# 04_-Power.net
KiCad netlist of a schematic drawn in Altium Designer
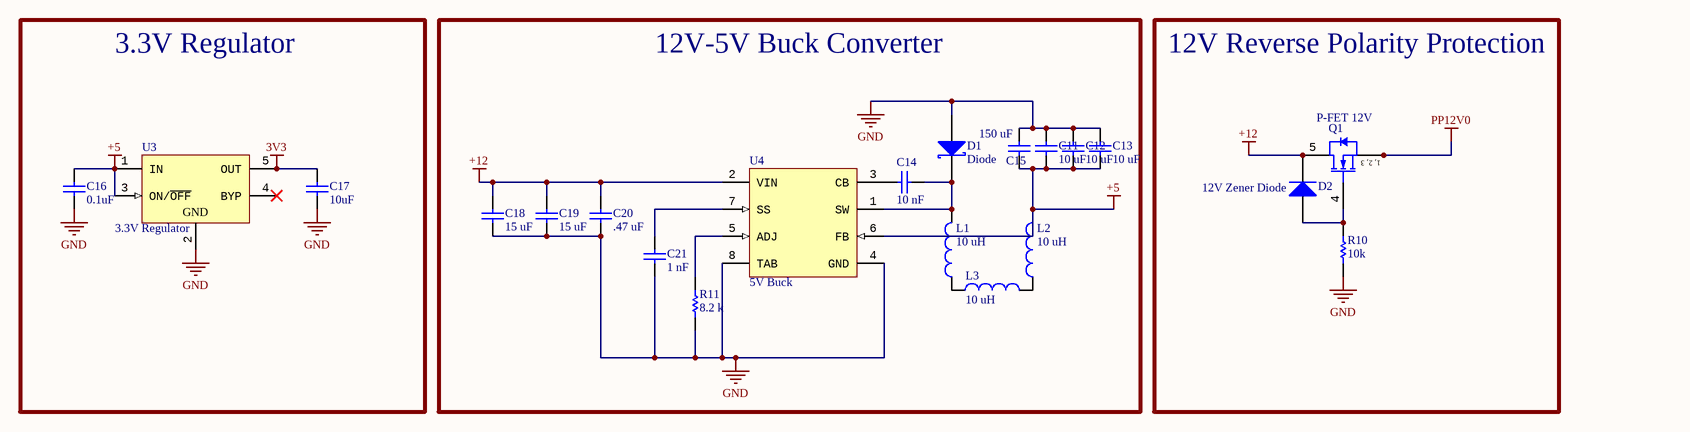
[diagram p0: [04]-Power.SchDoc]

(export (version "E")
  (design (tool "Eeschema 10.0.6"))
  (components
    (comp (ref "C11")
      (value "10 uF")
      (footprint "CAPC1608X90X38LL10T18")
      (description "Chip Capacitor, 10 uF, +/- 10%, 6.3 V, -55 to 85 degC, 0603 (1608 Metric), RoHS, Tape and Reel")
      (fields (field (name "MANUFACTURER") "Murata") (field (name "TOLERANCE") "10%"))
      (libsource (lib "Altium Content Vault") (part "CAP-NP-2"))
    )
    (comp (ref "C12")
      (value "10 uF")
      (footprint "CAPC1608X90X38LL10T18")
      (description "Chip Capacitor, 10 uF, +/- 10%, 6.3 V, -55 to 85 degC, 0603 (1608 Metric), RoHS, Tape and Reel")
      (fields (field (name "MANUFACTURER") "Murata") (field (name "TOLERANCE") "10%"))
      (libsource (lib "Altium Content Vault") (part "CAP-NP-2"))
    )
    (comp (ref "C13")
      (value "10 uF")
      (footprint "CAPC1608X90X38LL10T18")
      (description "Chip Capacitor, 10 uF, +/- 10%, 6.3 V, -55 to 85 degC, 0603 (1608 Metric), RoHS, Tape and Reel")
      (fields (field (name "MANUFACTURER") "Murata") (field (name "TOLERANCE") "10%"))
      (libsource (lib "Altium Content Vault") (part "CAP-NP-2"))
    )
    (comp (ref "C14")
      (value "10 nF")
      (footprint "CAPC2013X70X45ML10T25")
      (description "Chip Capacitor, 10 nF, +/- 10%, 50 V, -55 to 125 degC, 0805 (2012 Metric), RoHS, Tape and Reel")
      (fields (field (name "TOLERANCE") "10%") (field (name "MANUFACTURER") "Murata"))
      (libsource (lib "Altium Content Vault") (part "CAP-NP-2"))
    )
    (comp (ref "C15")
      (value "150 uF")
      (footprint "CAPC3216X180X50LL20T30")
      (description "Chip Capacitor, 10 uF, +/- 10%, 35 V, 1206 (3216 Metric), RoHS, Tape and Reel")
      (fields (field (name "TOLERANCE") "±20%") (field (name "MANUFACTURER") "Samsung Electro-Mechanics"))
      (libsource (lib "Altium Content Vault") (part "CAP-NP-2"))
    )
    (comp (ref "C16")
      (value "0.1uF")
      (footprint "CAPC2013X70X50ML10T25")
      (description "Chip Capacitor, 0.1 uF, -20% to 80%, 50 V, -30 to 85 degC, 0805 (2012 Metric), RoHS, Tape and Reel")
      (fields (field (name "MANUFACTURER") "Yageo") (field (name "TOLERANCE") "-20%,+80%"))
      (libsource (lib "Altium Content Vault") (part "CAP-NP-2"))
    )
    (comp (ref "C17")
      (value "10uF")
      (footprint "CAPC2013X145X50LL20T25")
      (description "Chip Capacitor, 10 uF, +/- 10%, 10 V, -55 to 85 degC, 0805 (2012 Metric), RoHS, Tape and Reel")
      (fields (field (name "MANUFACTURER") "Yageo") (field (name "TOLERANCE") "±10%"))
      (libsource (lib "Altium Content Vault") (part "CAP-NP-2"))
    )
    (comp (ref "C18")
      (value "15 uF")
      (footprint "CAPC5750X280X20LL40")
      (description "Chip Capacitor, 15 uF, +/- 20%, 100 V, -55 to 125 degC, 2220 (5750 Metric), RoHS, Tape and Reel")
      (fields (field (name "TOLERANCE") "20%") (field (name "MANUFACTURER") "TDK"))
      (libsource (lib "Altium Content Vault") (part "CAP-NP-2"))
    )
    (comp (ref "C19")
      (value "15 uF")
      (footprint "CAPC5750X280X20LL40")
      (description "Chip Capacitor, 15 uF, +/- 20%, 100 V, -55 to 125 degC, 2220 (5750 Metric), RoHS, Tape and Reel")
      (fields (field (name "TOLERANCE") "20%") (field (name "MANUFACTURER") "TDK"))
      (libsource (lib "Altium Content Vault") (part "CAP-NP-2"))
    )
    (comp (ref "C20")
      (value ".47 uF")
      (footprint "CAPC2013X95X50LL10T25")
      (description "Chip Capacitor, 0.47 uF, +/- 10%, 16 V, -55 to 125 degC, 0805 (2012 Metric), RoHS, Tape and Reel")
      (fields (field (name "MPN") "EMK212B7474KD-T") (field (name "MANUFACTURER") "Taiyo Yuden"))
      (libsource (lib "") (part "CAP-NP-2_1"))
    )
    (comp (ref "C21")
      (value "1 nF")
      (footprint "CAPC2013X70X50LL10T25")
      (description "Chip Capacitor, 1 nF, +/- 10%, 50 V, -55 to 125 degC, 0805 (2012 Metric), RoHS, Tape and Reel")
      (fields (field (name "TOLERANCE") "±10%") (field (name "MANUFACTURER") "Yageo"))
      (libsource (lib "Altium Content Vault") (part "CAP-NP-2"))
    )
    (comp (ref "D1")
      (value "Diode")
      (footprint "DIOD-SMA-2_A_V")
      (description "Schottky Barrier Rectifier, 50 V, 3 A, -55 to 150 degC, 2-Pin SMD, RoHS, Tape and Reel")
      (fields (field (name "MANUFACTURER") "DiodesIncorporated") (field (name "MPN") "B350A-13-F"))
      (libsource (lib "Altium Content Vault") (part "DSKY-AK-2"))
    )
    (comp (ref "D2")
      (value "12V Zener Diode")
      (footprint "FAIR-DO-214AA-2_V")
      (fields (field (name "MANUFACTURER") "Fairchild Semiconductor") (field (name "MPN") "SMBJ12A"))
      (libsource (lib "Altium Content Vault") (part "D-AK-2"))
    )
    (comp (ref "L1")
      (value "10 uH")
      (footprint "MURA-LQH32CN100K53")
      (description "Inductor, 10 uH, +/- 10%, 450 mA, -40 to 85 degC, 2-Pin SMD, RoHS, Tape and Reel")
      (fields (field (name "MANUFACTURER") "Murata") (field (name "TOLERANCE") "±10%"))
      (libsource (lib "Altium Content Vault") (part "IND-2"))
    )
    (comp (ref "L2")
      (value "10 uH")
      (footprint "MURA-LQH32CN100K53")
      (description "Inductor, 10 uH, +/- 10%, 450 mA, -40 to 85 degC, 2-Pin SMD, RoHS, Tape and Reel")
      (fields (field (name "MANUFACTURER") "Murata") (field (name "TOLERANCE") "±10%"))
      (libsource (lib "Altium Content Vault") (part "IND-2"))
    )
    (comp (ref "L3")
      (value "10 uH")
      (footprint "MURA-LQH32CN100K53")
      (description "Inductor, 10 uH, +/- 10%, 450 mA, -40 to 85 degC, 2-Pin SMD, RoHS, Tape and Reel")
      (fields (field (name "MANUFACTURER") "Murata") (field (name "TOLERANCE") "±10%"))
      (libsource (lib "Altium Content Vault") (part "IND-2"))
    )
    (comp (ref "Q1")
      (value "P-FET 12V")
      (footprint "NXP-SOT669_M")
      (description "N-Channel Logic Level MOSFET, 80 V, 25 A, 5-Pin SOT669, Tape and Reel")
      (fields (field (name "MANUFACTURER") "NXP Semiconductors") (field (name "PARTNUMBER") "PSMN041-80YLX"))
      (libsource (lib "Altium Content Vault") (part "NXP-NMOS-SSSGD-5"))
    )
    (comp (ref "R10")
      (value "10k")
      (footprint "RESC1005X40X25LL05T10")
      (fields (field (name "PART NUMBER") "RC0402FR-0710KL") (field (name "MANUFACTURER") "Yageo / Phycomp"))
      (libsource (lib "Altium Content Vault") (part "RES"))
    )
    (comp (ref "R11")
      (value "8.2 k")
      (footprint "RESC2013X50X40LL20T20")
      (fields (field (name "MPN") "RR1220P-822-D") (field (name "MANUFACTURER") "Susumu"))
      (libsource (lib "Altium Content Vault") (part "RES"))
    )
    (comp (ref "U3")
      (value "3.3V Regulator")
      (footprint "MF05A_M")
      (description "Micropower 50 mA Ultra Low-Dropout Regulator, 5-pin SOT-23")
      (fields
        (field (name "MANUFACTURER") "National Semiconductor")
        (field (name "MPN") "LP2982AIM5-3.3/NOPB")
      )
      (libsource (lib "Altium Content Vault") (part "PM-REG-LP2982-SOT5"))
    )
    (comp (ref "U4")
      (value "5V Buck")
      (footprint "TS7B_N")
      (description "3A Step-Down Voltage Regulator with Adjustable Current Limit, 7-pin TO-263")
      (fields (field (name "MANUFACTURER") "Texas Instruments") (field (name "MPN") "LM2673S-5.0/NOPB"))
      (libsource (lib "Altium Content Vault") (part "PM-REG-LM2673S"))
    )
  )
  (nets
    (net (code "1") (name "+5") (class "Default")
      (node (ref "C11") (pin "1") (pinfunction "1_1") (pintype "passive"))
      (node (ref "C12") (pin "1") (pinfunction "1_1") (pintype "passive"))
      (node (ref "C13") (pin "1") (pinfunction "1_1") (pintype "passive"))
      (node (ref "C15") (pin "1") (pinfunction "1_1") (pintype "passive"))
      (node (ref "C16") (pin "2") (pinfunction "2_2") (pintype "passive"))
      (node (ref "L2") (pin "2") (pinfunction "2_2") (pintype "passive"))
      (node (ref "U3") (pin "1") (pinfunction "IN_1") (pintype "power_in"))
      (node (ref "U3") (pin "3") (pinfunction "ON/~{OFF}_3") (pintype "input"))
      (node (ref "U4") (pin "6") (pinfunction "FB_6") (pintype "input"))
    )
    (net (code "2") (name "+12") (class "Default")
      (node (ref "C18") (pin "2") (pinfunction "2_2") (pintype "passive"))
      (node (ref "C19") (pin "2") (pinfunction "2_2") (pintype "passive"))
      (node (ref "C20") (pin "1") (pinfunction "1_1") (pintype "passive"))
      (node (ref "D2") (pin "2") (pinfunction "K_2") (pintype "passive"))
      (node (ref "Q1") (pin "5") (pinfunction "D_5") (pintype "passive"))
      (node (ref "U4") (pin "2") (pinfunction "VIN_2") (pintype "power_in"))
    )
    (net (code "3") (name "3V3") (class "Default")
      (node (ref "C17") (pin "2") (pinfunction "2_2") (pintype "passive"))
      (node (ref "U3") (pin "5") (pinfunction "OUT_5") (pintype "power_in"))
    )
    (net (code "4") (name "GND") (class "Default")
      (node (ref "C11") (pin "2") (pinfunction "2_2") (pintype "passive"))
      (node (ref "C12") (pin "2") (pinfunction "2_2") (pintype "passive"))
      (node (ref "C13") (pin "2") (pinfunction "2_2") (pintype "passive"))
      (node (ref "C15") (pin "2") (pinfunction "2_2") (pintype "passive"))
      (node (ref "C16") (pin "1") (pinfunction "1_1") (pintype "passive"))
      (node (ref "C17") (pin "1") (pinfunction "1_1") (pintype "passive"))
      (node (ref "C18") (pin "1") (pinfunction "1_1") (pintype "passive"))
      (node (ref "C19") (pin "1") (pinfunction "1_1") (pintype "passive"))
      (node (ref "C20") (pin "2") (pinfunction "2_2") (pintype "passive"))
      (node (ref "C21") (pin "1") (pinfunction "1_1") (pintype "passive"))
      (node (ref "D1") (pin "1") (pinfunction "A_1") (pintype "passive"))
      (node (ref "R10") (pin "1") (pinfunction "1_1") (pintype "passive"))
      (node (ref "R11") (pin "1") (pinfunction "1_1") (pintype "passive"))
      (node (ref "U3") (pin "2") (pinfunction "GND_2") (pintype "power_in"))
      (node (ref "U4") (pin "4") (pinfunction "GND_4") (pintype "power_in"))
      (node (ref "U4") (pin "8") (pinfunction "TAB_8") (pintype "power_in"))
    )
    (net (code "5") (name "Net-(D1-K)") (class "Default")
      (node (ref "C14") (pin "2") (pinfunction "2_2") (pintype "passive"))
      (node (ref "D1") (pin "2") (pinfunction "K_2") (pintype "passive"))
      (node (ref "L1") (pin "2") (pinfunction "2_2") (pintype "passive"))
      (node (ref "U4") (pin "1") (pinfunction "SW_1") (pintype "power_in"))
    )
    (net (code "6") (name "Net-(D2-A)") (class "Default")
      (node (ref "D2") (pin "1") (pinfunction "A_1") (pintype "passive"))
      (node (ref "Q1") (pin "4") (pinfunction "G_4") (pintype "passive"))
      (node (ref "R10") (pin "2") (pinfunction "2_2") (pintype "passive"))
    )
    (net (code "7") (name "Net-(L1-Pad1)") (class "Default")
      (node (ref "L1") (pin "1") (pinfunction "1_1") (pintype "passive"))
      (node (ref "L3") (pin "1") (pinfunction "1_1") (pintype "passive"))
    )
    (net (code "8") (name "Net-(L2-Pad1)") (class "Default")
      (node (ref "L2") (pin "1") (pinfunction "1_1") (pintype "passive"))
      (node (ref "L3") (pin "2") (pinfunction "2_2") (pintype "passive"))
    )
    (net (code "9") (name "Net-(U4-ADJ)") (class "Default")
      (node (ref "R11") (pin "2") (pinfunction "2_2") (pintype "passive"))
      (node (ref "U4") (pin "5") (pinfunction "ADJ_5") (pintype "input"))
    )
    (net (code "10") (name "Net-(U4-CB)") (class "Default")
      (node (ref "C14") (pin "1") (pinfunction "1_1") (pintype "passive"))
      (node (ref "U4") (pin "3") (pinfunction "CB_3") (pintype "passive"))
    )
    (net (code "11") (name "Net-(U4-SS)") (class "Default")
      (node (ref "C21") (pin "2") (pinfunction "2_2") (pintype "passive"))
      (node (ref "U4") (pin "7") (pinfunction "SS_7") (pintype "input"))
    )
    (net (code "12") (name "PP12V0") (class "Default")
      (node (ref "Q1") (pin "1") (pinfunction "S_1") (pintype "passive"))
      (node (ref "Q1") (pin "2") (pinfunction "S_2") (pintype "passive"))
      (node (ref "Q1") (pin "3") (pinfunction "S_3") (pintype "passive"))
    )
    (net (code "13") (name "unconnected-(U3-BYP-Pad4)") (class "Default")
      (node (ref "U3") (pin "4") (pinfunction "BYP_4") (pintype "passive+no_connect"))
    )
  )
)
